# Supply.net
KiCad netlist of a schematic drawn in Altium Designer
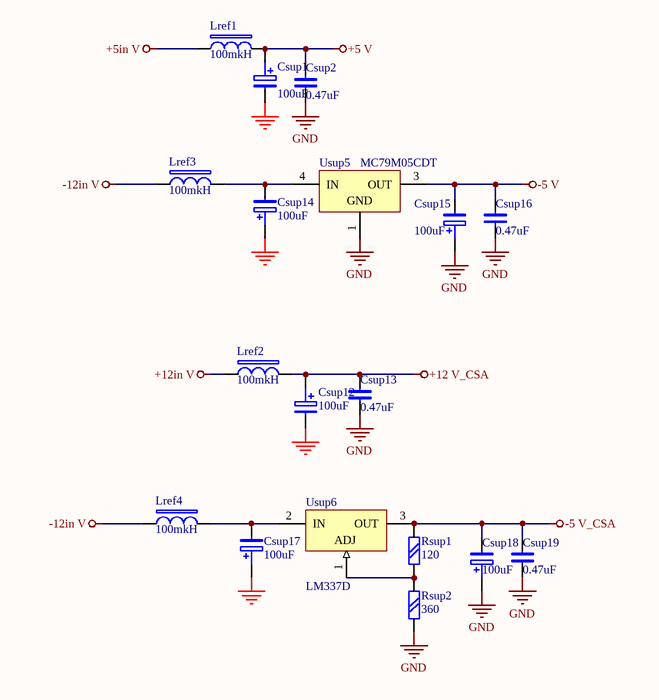
[diagram p0: Supply.SchDoc]

(export (version "E")
  (design (tool "Eeschema 10.0.6"))
  (components
    (comp (ref "Csup1") (value "100uF") (footprint "CEL-SMD300") (libsource (lib "*") (part "C POL")))
    (comp (ref "Csup2") (value "0.47uF") (footprint "chip0805") (libsource (lib "*") (part "C")))
    (comp (ref "Csup12") (value "100uF") (footprint "CEL-SMD300") (libsource (lib "*") (part "C POL")))
    (comp (ref "Csup13") (value "0.47uF") (footprint "chip0805") (libsource (lib "*") (part "C")))
    (comp (ref "Csup14") (value "100uF") (footprint "CEL-SMD300") (libsource (lib "*") (part "C POL")))
    (comp (ref "Csup15") (value "100uF") (footprint "CEL-SMD300") (libsource (lib "*") (part "C POL")))
    (comp (ref "Csup16") (value "0.47uF") (footprint "chip0805") (libsource (lib "*") (part "C")))
    (comp (ref "Csup17") (value "100uF") (footprint "CEL-SMD300") (libsource (lib "*") (part "C POL")))
    (comp (ref "Csup18") (value "100uF") (footprint "CEL-SMD300") (libsource (lib "*") (part "C POL")))
    (comp (ref "Csup19") (value "0.47uF") (footprint "chip0805") (libsource (lib "*") (part "C")))
    (comp (ref "Lref1") (value "100mkH") (footprint "SDR0604") (libsource (lib "*") (part "DR")))
    (comp (ref "Lref2") (value "100mkH") (footprint "SDR0604") (libsource (lib "*") (part "DR")))
    (comp (ref "Lref3") (value "100mkH") (footprint "SDR0604") (libsource (lib "*") (part "DR")))
    (comp (ref "Lref4") (value "100mkH") (footprint "SDR0604") (libsource (lib "*") (part "DR")))
    (comp (ref "Rsup1") (value "120") (footprint "chip0805") (libsource (lib "vDevice") (part "R")))
    (comp (ref "Rsup2") (value "360") (footprint "chip0805") (libsource (lib "vDevice") (part "R")))
    (comp (ref "Usup5")
      (value "MC79M05CDT")
      (footprint "369A-13")
      (description "Three-Terminal Negative Voltage Regulator")
      (fields (field (name "PUBLISHER") "Altium Limited"))
      (libsource (lib "ON Semi Power Mgt Voltage Regulator") (part "MC79M05CDT"))
    )
    (comp (ref "Usup6")
      (value "LM337D")
      (footprint "TO-220B")
      (description "Three-Terminal Adjustable Output Negative Voltage")
      (fields (field (name "PUBLISHER") "Altium Limited"))
      (libsource (lib "ON Semi Power Mgt Voltage Regulator") (part "LM337T"))
    )
  )
  (nets
    (net (code "1") (name "+5 V") (class "Default")
      (node (ref "Csup1") (pin "+") (pinfunction "+_+") (pintype "passive"))
      (node (ref "Csup2") (pin "1") (pinfunction "1_1") (pintype "passive"))
      (node (ref "Lref1") (pin "2") (pinfunction "2_2") (pintype "passive"))
    )
    (net (code "2") (name "+5in V") (class "Default")
      (node (ref "Lref1") (pin "1") (pinfunction "1_1") (pintype "passive"))
    )
    (net (code "3") (name "+12 V_CSA") (class "Default")
      (node (ref "Csup12") (pin "+") (pinfunction "+_+") (pintype "passive"))
      (node (ref "Csup13") (pin "1") (pinfunction "1_1") (pintype "passive"))
      (node (ref "Lref2") (pin "2") (pinfunction "2_2") (pintype "passive"))
    )
    (net (code "4") (name "+12in V") (class "Default")
      (node (ref "Lref2") (pin "1") (pinfunction "1_1") (pintype "passive"))
    )
    (net (code "5") (name "-5 V") (class "Default")
      (node (ref "Csup15") (pin "-") (pinfunction "-_-") (pintype "passive"))
      (node (ref "Csup16") (pin "1") (pinfunction "1_1") (pintype "passive"))
      (node (ref "Usup5") (pin "3") (pinfunction "OUT_3") (pintype "power_in"))
    )
    (net (code "6") (name "-5 V_CSA") (class "Default")
      (node (ref "Csup18") (pin "-") (pinfunction "-_-") (pintype "passive"))
      (node (ref "Csup19") (pin "1") (pinfunction "1_1") (pintype "passive"))
      (node (ref "Rsup1") (pin "1") (pinfunction "1_1") (pintype "passive"))
      (node (ref "Usup6") (pin "3") (pinfunction "OUT_3") (pintype "power_in"))
    )
    (net (code "7") (name "-12in V") (class "Default")
      (node (ref "Lref3") (pin "1") (pinfunction "1_1") (pintype "passive"))
      (node (ref "Lref4") (pin "1") (pinfunction "1_1") (pintype "passive"))
    )
    (net (code "8") (name "GND") (class "Default")
      (node (ref "Csup1") (pin "-") (pinfunction "-_-") (pintype "passive"))
      (node (ref "Csup12") (pin "-") (pinfunction "-_-") (pintype "passive"))
      (node (ref "Csup13") (pin "2") (pinfunction "2_2") (pintype "passive"))
      (node (ref "Csup14") (pin "+") (pinfunction "+_+") (pintype "passive"))
      (node (ref "Csup15") (pin "+") (pinfunction "+_+") (pintype "passive"))
      (node (ref "Csup16") (pin "2") (pinfunction "2_2") (pintype "passive"))
      (node (ref "Csup17") (pin "+") (pinfunction "+_+") (pintype "passive"))
      (node (ref "Csup18") (pin "+") (pinfunction "+_+") (pintype "passive"))
      (node (ref "Csup19") (pin "2") (pinfunction "2_2") (pintype "passive"))
      (node (ref "Csup2") (pin "2") (pinfunction "2_2") (pintype "passive"))
      (node (ref "Rsup2") (pin "2") (pinfunction "2_2") (pintype "passive"))
      (node (ref "Usup5") (pin "1") (pinfunction "GND_1") (pintype "power_in"))
    )
    (net (code "9") (name "Net-(Usup5-IN)") (class "Default")
      (node (ref "Csup14") (pin "-") (pinfunction "-_-") (pintype "passive"))
      (node (ref "Lref3") (pin "2") (pinfunction "2_2") (pintype "passive"))
      (node (ref "Usup5") (pin "4") (pinfunction "IN_4") (pintype "power_in"))
    )
    (net (code "10") (name "Net-(Usup6-ADJ)") (class "Default")
      (node (ref "Rsup1") (pin "2") (pinfunction "2_2") (pintype "passive"))
      (node (ref "Rsup2") (pin "1") (pinfunction "1_1") (pintype "passive"))
      (node (ref "Usup6") (pin "1") (pinfunction "ADJ_1") (pintype "input"))
    )
    (net (code "11") (name "Net-(Usup6-IN)") (class "Default")
      (node (ref "Csup17") (pin "-") (pinfunction "-_-") (pintype "passive"))
      (node (ref "Lref4") (pin "2") (pinfunction "2_2") (pintype "passive"))
      (node (ref "Usup6") (pin "2") (pinfunction "IN_2") (pintype "power_in"))
    )
  )
)
